# temp-monitor.net
KiCad netlist of a schematic drawn in EAGLE
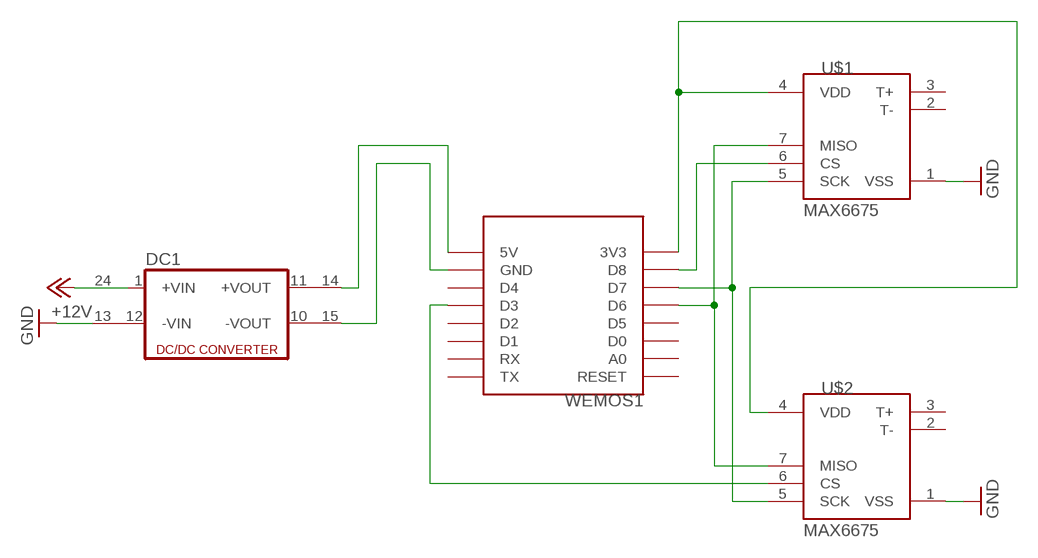
[diagram p0: schematic, sheet 1]

(export (version "E")
  (design (tool "Eeschema 10.0.6"))
  (components
    (comp (ref "DC1")
      (value "DC213R")
      (footprint "eagle-import:CMK")
      (libsource (lib "eagle-import") (part "DC213R"))
    )
    (comp (ref "U$1")
      (value "MAX6675")
      (footprint "eagle-import:SO08")
      (libsource (lib "eagle-import") (part "MAX6675"))
    )
    (comp (ref "U$2")
      (value "MAX6675")
      (footprint "eagle-import:SO08")
      (libsource (lib "eagle-import") (part "MAX6675"))
    )
    (comp (ref "WEMOS1")
      (value "WEMOS-D1-MINI")
      (footprint "eagle-import:WEMOS-D1-MINI")
      (libsource (lib "eagle-import") (part "WEMOS-D1-MINI"))
    )
  )
  (nets
    (net (code "1") (name "+12V") (class "Default")
      (node (ref "DC1") (pin "1") (pinfunction "+VIN_1") (pintype "passive"))
      (node (ref "DC1") (pin "24") (pinfunction "+VIN1_24") (pintype "passive"))
    )
    (net (code "2") (name "GND") (class "Default")
      (node (ref "DC1") (pin "13") (pinfunction "-VIN1_13") (pintype "passive"))
      (node (ref "U$1") (pin "1") (pinfunction "VSS_1") (pintype "bidirectional"))
      (node (ref "U$2") (pin "1") (pinfunction "VSS_1") (pintype "bidirectional"))
    )
    (net (code "3") (name "Net-(DC1-+VOUT1)") (class "Default")
      (node (ref "DC1") (pin "14") (pinfunction "+VOUT1_14") (pintype "passive"))
      (node (ref "WEMOS1") (pin "5V") (pinfunction "5V_5V") (pintype "bidirectional"))
    )
    (net (code "4") (name "Net-(DC1--VOUT1)") (class "Default")
      (node (ref "DC1") (pin "15") (pinfunction "-VOUT1_15") (pintype "passive"))
      (node (ref "WEMOS1") (pin "GND") (pinfunction "GND_GND") (pintype "bidirectional"))
    )
    (net (code "5") (name "Net-(U$1-CS)") (class "Default")
      (node (ref "U$1") (pin "6") (pinfunction "CS_6") (pintype "bidirectional"))
      (node (ref "WEMOS1") (pin "D8") (pinfunction "D8_D8") (pintype "bidirectional"))
    )
    (net (code "6") (name "Net-(U$1-MISO)") (class "Default")
      (node (ref "U$1") (pin "7") (pinfunction "MISO_7") (pintype "bidirectional"))
      (node (ref "U$2") (pin "7") (pinfunction "MISO_7") (pintype "bidirectional"))
      (node (ref "WEMOS1") (pin "D6") (pinfunction "D6_D6") (pintype "bidirectional"))
    )
    (net (code "7") (name "Net-(U$1-SCK)") (class "Default")
      (node (ref "U$1") (pin "5") (pinfunction "SCK_5") (pintype "bidirectional"))
      (node (ref "U$2") (pin "5") (pinfunction "SCK_5") (pintype "bidirectional"))
      (node (ref "WEMOS1") (pin "D7") (pinfunction "D7_D7") (pintype "bidirectional"))
    )
    (net (code "8") (name "Net-(U$1-VDD)") (class "Default")
      (node (ref "U$1") (pin "4") (pinfunction "VDD_4") (pintype "bidirectional"))
      (node (ref "U$2") (pin "4") (pinfunction "VDD_4") (pintype "bidirectional"))
      (node (ref "WEMOS1") (pin "3V3") (pinfunction "3V3_3V3") (pintype "bidirectional"))
    )
    (net (code "9") (name "Net-(U$2-CS)") (class "Default")
      (node (ref "U$2") (pin "6") (pinfunction "CS_6") (pintype "bidirectional"))
      (node (ref "WEMOS1") (pin "D3") (pinfunction "D3_D3") (pintype "bidirectional"))
    )
    (net (code "10") (name "unconnected-(DC1-+VOUT-Pad11)") (class "Default")
      (node (ref "DC1") (pin "11") (pinfunction "+VOUT_11") (pintype "passive"))
    )
    (net (code "11") (name "unconnected-(DC1--VIN-Pad12)") (class "Default")
      (node (ref "DC1") (pin "12") (pinfunction "-VIN_12") (pintype "passive"))
    )
    (net (code "12") (name "unconnected-(DC1--VOUT-Pad10)") (class "Default")
      (node (ref "DC1") (pin "10") (pinfunction "-VOUT_10") (pintype "passive"))
    )
    (net (code "13") (name "unconnected-(U$1-T+-Pad3)") (class "Default")
      (node (ref "U$1") (pin "3") (pinfunction "T+_3") (pintype "bidirectional"))
    )
    (net (code "14") (name "unconnected-(U$1-T--Pad2)") (class "Default")
      (node (ref "U$1") (pin "2") (pinfunction "T-_2") (pintype "bidirectional"))
    )
    (net (code "15") (name "unconnected-(U$2-T+-Pad3)") (class "Default")
      (node (ref "U$2") (pin "3") (pinfunction "T+_3") (pintype "bidirectional"))
    )
    (net (code "16") (name "unconnected-(U$2-T--Pad2)") (class "Default")
      (node (ref "U$2") (pin "2") (pinfunction "T-_2") (pintype "bidirectional"))
    )
    (net (code "17") (name "unconnected-(WEMOS1-PadA0)") (class "Default")
      (node (ref "WEMOS1") (pin "A0") (pinfunction "A0_A0") (pintype "bidirectional"))
    )
    (net (code "18") (name "unconnected-(WEMOS1-PadD0)") (class "Default")
      (node (ref "WEMOS1") (pin "D0") (pinfunction "D0_D0") (pintype "bidirectional"))
    )
    (net (code "19") (name "unconnected-(WEMOS1-PadD1)") (class "Default")
      (node (ref "WEMOS1") (pin "D1") (pinfunction "D1_D1") (pintype "bidirectional"))
    )
    (net (code "20") (name "unconnected-(WEMOS1-PadD2)") (class "Default")
      (node (ref "WEMOS1") (pin "D2") (pinfunction "D2_D2") (pintype "bidirectional"))
    )
    (net (code "21") (name "unconnected-(WEMOS1-PadD4)") (class "Default")
      (node (ref "WEMOS1") (pin "D4") (pinfunction "D4_D4") (pintype "bidirectional"))
    )
    (net (code "22") (name "unconnected-(WEMOS1-PadD5)") (class "Default")
      (node (ref "WEMOS1") (pin "D5") (pinfunction "D5_D5") (pintype "bidirectional"))
    )
    (net (code "23") (name "unconnected-(WEMOS1-PadRESET)") (class "Default")
      (node (ref "WEMOS1") (pin "RESET") (pinfunction "RESET_RESET") (pintype "bidirectional"))
    )
    (net (code "24") (name "unconnected-(WEMOS1-PadRX)") (class "Default")
      (node (ref "WEMOS1") (pin "RX") (pinfunction "RX_RX") (pintype "bidirectional"))
    )
    (net (code "25") (name "unconnected-(WEMOS1-PadTX)") (class "Default")
      (node (ref "WEMOS1") (pin "TX") (pinfunction "TX_TX") (pintype "bidirectional"))
    )
  )
)
